# mouse.net
KiCad netlist of a schematic drawn in Altium Designer
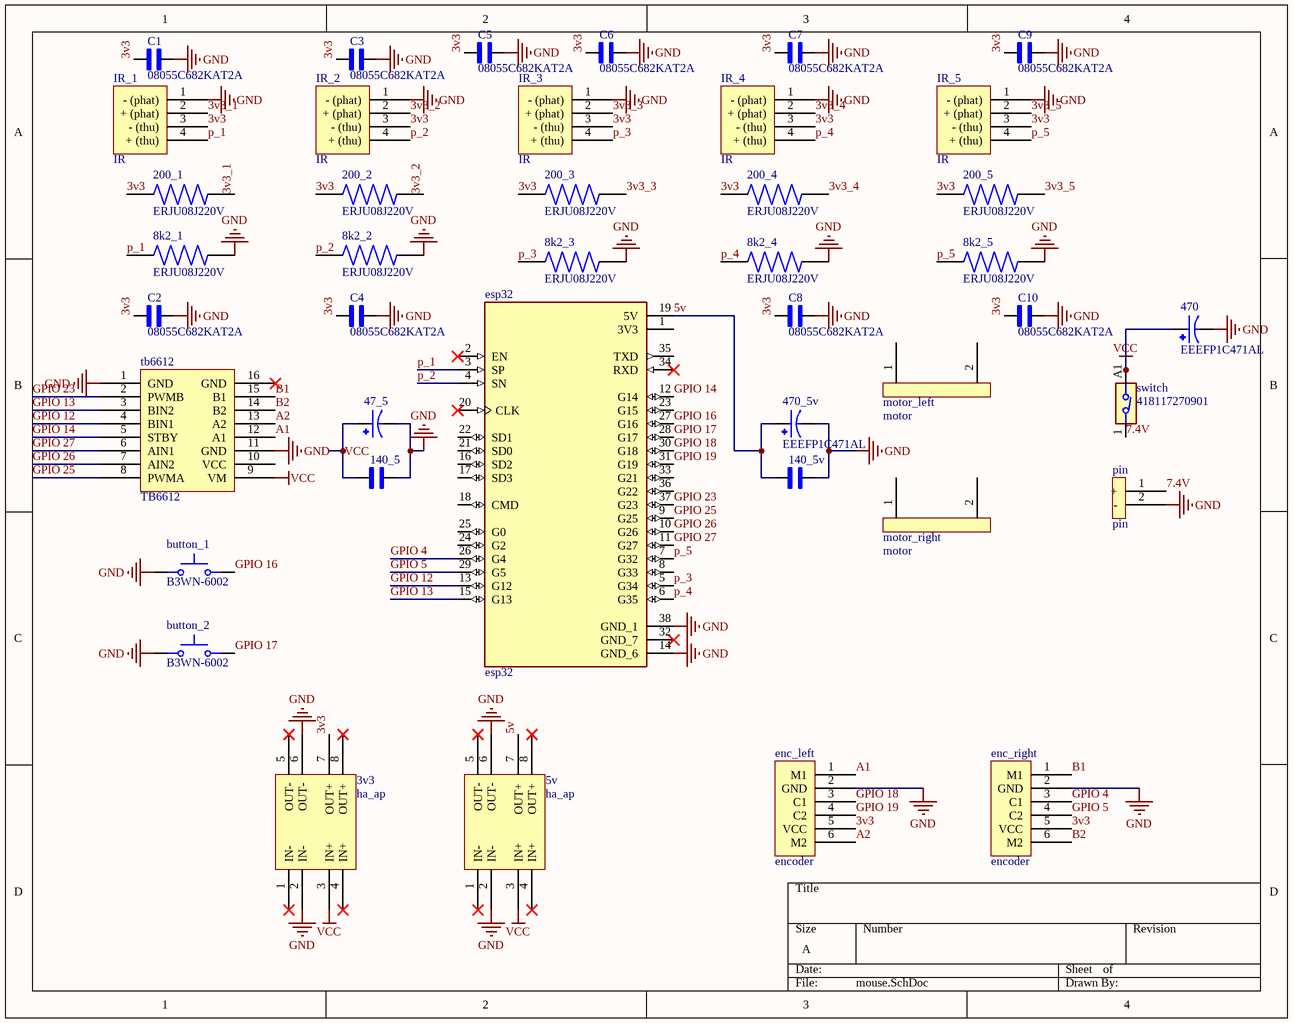
[diagram p0: mouse.SchDoc]

(export (version "E")
  (design (tool "Eeschema 10.0.6"))
  (components
    (comp (ref "3v3") (value "ha_ap") (footprint "ha_ap") (libsource (lib "mouse") (part "ha_ap")))
    (comp (ref "5v") (value "ha_ap") (footprint "ha_ap") (libsource (lib "mouse") (part "ha_ap")))
    (comp (ref "8k2_1")
      (value "ERJU08J220V")
      (footprint "RES_ERJU08J220V")
      (libsource (lib "ERJU08J220V") (part "ERJU08J220V"))
    )
    (comp (ref "8k2_2")
      (value "ERJU08J220V")
      (footprint "RES_ERJU08J220V")
      (libsource (lib "ERJU08J220V") (part "ERJU08J220V"))
    )
    (comp (ref "8k2_3")
      (value "ERJU08J220V")
      (footprint "RES_ERJU08J220V")
      (libsource (lib "ERJU08J220V") (part "ERJU08J220V"))
    )
    (comp (ref "8k2_4")
      (value "ERJU08J220V")
      (footprint "RES_ERJU08J220V")
      (libsource (lib "ERJU08J220V") (part "ERJU08J220V"))
    )
    (comp (ref "8k2_5")
      (value "ERJU08J220V")
      (footprint "RES_ERJU08J220V")
      (libsource (lib "ERJU08J220V") (part "ERJU08J220V"))
    )
    (comp (ref "47_5")
      (value "EEEFK1C470V")
      (footprint "CAP_EEEFK1C470V")
      (description "CAP ALUM 47UF 20% 16V SMD")
      (fields (field (name "MF") "Panasonic"))
      (libsource (lib "EEEFK1C470V") (part "EEEFK1C470V"))
    )
    (comp (ref "140_5")
      (value "08055C682KAT2A")
      (footprint "CAPC2012X94N")
      (description "Capacitor MLCC 0805 6.8nF 50V ¦ AVX 08055C682KAT2A")
      (fields (field (name "MF") "AVX"))
      (libsource (lib "08055C682KAT2A") (part "08055C682KAT2A"))
    )
    (comp (ref "140_5v")
      (value "08055C682KAT2A")
      (footprint "CAPC2012X94N")
      (description "Capacitor MLCC 0805 6.8nF 50V ¦ AVX 08055C682KAT2A")
      (fields (field (name "MF") "AVX"))
      (libsource (lib "08055C682KAT2A") (part "08055C682KAT2A"))
    )
    (comp (ref "200_1")
      (value "ERJU08J220V")
      (footprint "RES_ERJU08J220V")
      (libsource (lib "ERJU08J220V") (part "ERJU08J220V"))
    )
    (comp (ref "200_2")
      (value "ERJU08J220V")
      (footprint "RES_ERJU08J220V")
      (libsource (lib "ERJU08J220V") (part "ERJU08J220V"))
    )
    (comp (ref "200_3")
      (value "ERJU08J220V")
      (footprint "RES_ERJU08J220V")
      (libsource (lib "ERJU08J220V") (part "ERJU08J220V"))
    )
    (comp (ref "200_4")
      (value "ERJU08J220V")
      (footprint "RES_ERJU08J220V")
      (libsource (lib "ERJU08J220V") (part "ERJU08J220V"))
    )
    (comp (ref "200_5")
      (value "ERJU08J220V")
      (footprint "RES_ERJU08J220V")
      (libsource (lib "ERJU08J220V") (part "ERJU08J220V"))
    )
    (comp (ref "470")
      (value "EEEFP1C471AL")
      (footprint "CAP_EEEFP1C471AL")
      (description "CAP ALUM 470UF 20% 16V SMD")
      (fields (field (name "MF") "Panasonic"))
      (libsource (lib "EEEFP1C471AL") (part "EEEFP1C471AL"))
    )
    (comp (ref "470_5v")
      (value "EEEFP1C471AL")
      (footprint "CAP_EEEFP1C471AL")
      (description "CAP ALUM 470UF 20% 16V SMD")
      (fields (field (name "MF") "Panasonic"))
      (libsource (lib "EEEFP1C471AL") (part "EEEFP1C471AL"))
    )
    (comp (ref "button_1")
      (value "B3WN-6002")
      (footprint "SW_B3WN-6002")
      (description "Tactile Switch SPST-NO Top Actuated Through Hole")
      (fields (field (name "MF") "Omron Electronics"))
      (libsource (lib "B3WN-6002") (part "B3WN-6002"))
    )
    (comp (ref "button_2")
      (value "B3WN-6002")
      (footprint "SW_B3WN-6002")
      (description "Tactile Switch SPST-NO Top Actuated Through Hole")
      (fields (field (name "MF") "Omron Electronics"))
      (libsource (lib "B3WN-6002") (part "B3WN-6002"))
    )
    (comp (ref "C1")
      (value "08055C682KAT2A")
      (footprint "CAPC2012X94N")
      (description "Capacitor MLCC 0805 6.8nF 50V ¦ AVX 08055C682KAT2A")
      (fields (field (name "MF") "AVX"))
      (libsource (lib "08055C682KAT2A") (part "08055C682KAT2A"))
    )
    (comp (ref "C2")
      (value "08055C682KAT2A")
      (footprint "CAPC2012X94N")
      (description "Capacitor MLCC 0805 6.8nF 50V ¦ AVX 08055C682KAT2A")
      (fields (field (name "MF") "AVX"))
      (libsource (lib "08055C682KAT2A") (part "08055C682KAT2A"))
    )
    (comp (ref "C3")
      (value "08055C682KAT2A")
      (footprint "CAPC2012X94N")
      (description "Capacitor MLCC 0805 6.8nF 50V ¦ AVX 08055C682KAT2A")
      (fields (field (name "MF") "AVX"))
      (libsource (lib "08055C682KAT2A") (part "08055C682KAT2A"))
    )
    (comp (ref "C4")
      (value "08055C682KAT2A")
      (footprint "CAPC2012X94N")
      (description "Capacitor MLCC 0805 6.8nF 50V ¦ AVX 08055C682KAT2A")
      (fields (field (name "MF") "AVX"))
      (libsource (lib "08055C682KAT2A") (part "08055C682KAT2A"))
    )
    (comp (ref "C5")
      (value "08055C682KAT2A")
      (footprint "CAPC2012X94N")
      (description "Capacitor MLCC 0805 6.8nF 50V ¦ AVX 08055C682KAT2A")
      (fields (field (name "MF") "AVX"))
      (libsource (lib "08055C682KAT2A") (part "08055C682KAT2A"))
    )
    (comp (ref "C6")
      (value "08055C682KAT2A")
      (footprint "CAPC2012X94N")
      (description "Capacitor MLCC 0805 6.8nF 50V ¦ AVX 08055C682KAT2A")
      (fields (field (name "MF") "AVX"))
      (libsource (lib "08055C682KAT2A") (part "08055C682KAT2A"))
    )
    (comp (ref "C7")
      (value "08055C682KAT2A")
      (footprint "CAPC2012X94N")
      (description "Capacitor MLCC 0805 6.8nF 50V ¦ AVX 08055C682KAT2A")
      (fields (field (name "MF") "AVX"))
      (libsource (lib "08055C682KAT2A") (part "08055C682KAT2A"))
    )
    (comp (ref "C8")
      (value "08055C682KAT2A")
      (footprint "CAPC2012X94N")
      (description "Capacitor MLCC 0805 6.8nF 50V ¦ AVX 08055C682KAT2A")
      (fields (field (name "MF") "AVX"))
      (libsource (lib "08055C682KAT2A") (part "08055C682KAT2A"))
    )
    (comp (ref "C9")
      (value "08055C682KAT2A")
      (footprint "CAPC2012X94N")
      (description "Capacitor MLCC 0805 6.8nF 50V ¦ AVX 08055C682KAT2A")
      (fields (field (name "MF") "AVX"))
      (libsource (lib "08055C682KAT2A") (part "08055C682KAT2A"))
    )
    (comp (ref "C10")
      (value "08055C682KAT2A")
      (footprint "CAPC2012X94N")
      (description "Capacitor MLCC 0805 6.8nF 50V ¦ AVX 08055C682KAT2A")
      (fields (field (name "MF") "AVX"))
      (libsource (lib "08055C682KAT2A") (part "08055C682KAT2A"))
    )
    (comp (ref "enc_left") (value "encoder") (footprint "encoder") (libsource (lib "mouse") (part "encoder")))
    (comp (ref "enc_right")
      (value "encoder")
      (footprint "encoder")
      (libsource (lib "mouse") (part "encoder"))
    )
    (comp (ref "esp32") (value "esp32") (footprint "esp32") (libsource (lib "mouse") (part "esp32")))
    (comp (ref "IR_1") (value "IR") (footprint "IR") (libsource (lib "mouse") (part "IR")))
    (comp (ref "IR_2") (value "IR") (footprint "IR") (libsource (lib "mouse") (part "IR")))
    (comp (ref "IR_3") (value "IR") (footprint "IR") (libsource (lib "mouse") (part "IR")))
    (comp (ref "IR_4") (value "IR") (footprint "IR") (libsource (lib "mouse") (part "IR")))
    (comp (ref "IR_5") (value "IR") (footprint "IR") (libsource (lib "mouse") (part "IR")))
    (comp (ref "motor_left") (value "motor") (footprint "motor") (libsource (lib "mouse") (part "motor")))
    (comp (ref "motor_right") (value "motor") (footprint "motor") (libsource (lib "mouse") (part "motor")))
    (comp (ref "pin") (value "pin") (footprint "pin") (libsource (lib "mouse") (part "pin")))
    (comp (ref "switch")
      (value "418117270901")
      (footprint "418117270901")
      (description "Dip Switch SPST 1 Position Through Hole Slide (Standard) Actuator 25mA 24VDC")
      (fields (field (name "MF") "WÃ¼rth Elektronik"))
      (libsource (lib "418117270901") (part "418117270901"))
    )
    (comp (ref "tb6612") (value "TB6612") (footprint "TB6612") (libsource (lib "mouse") (part "TB6612")))
  )
  (nets
    (net (code "1") (name "/3v3") (class "Default")
      (node (ref "200_1") (pin "1") (pinfunction "1_1") (pintype "passive"))
      (node (ref "200_2") (pin "1") (pinfunction "1_1") (pintype "passive"))
      (node (ref "200_3") (pin "1") (pinfunction "1_1") (pintype "passive"))
      (node (ref "200_4") (pin "1") (pinfunction "1_1") (pintype "passive"))
      (node (ref "200_5") (pin "1") (pinfunction "1_1") (pintype "passive"))
      (node (ref "3v3") (pin "7") (pinfunction "OUT+_7") (pintype "passive"))
      (node (ref "C1") (pin "1") (pinfunction "1_1") (pintype "passive"))
      (node (ref "C10") (pin "1") (pinfunction "1_1") (pintype "passive"))
      (node (ref "C2") (pin "1") (pinfunction "1_1") (pintype "passive"))
      (node (ref "C3") (pin "1") (pinfunction "1_1") (pintype "passive"))
      (node (ref "C4") (pin "1") (pinfunction "1_1") (pintype "passive"))
      (node (ref "C5") (pin "1") (pinfunction "1_1") (pintype "passive"))
      (node (ref "C6") (pin "1") (pinfunction "1_1") (pintype "passive"))
      (node (ref "C7") (pin "1") (pinfunction "1_1") (pintype "passive"))
      (node (ref "C8") (pin "1") (pinfunction "1_1") (pintype "passive"))
      (node (ref "C9") (pin "1") (pinfunction "1_1") (pintype "passive"))
      (node (ref "IR_1") (pin "3") (pinfunction "-_(thu)_3") (pintype "passive"))
      (node (ref "IR_2") (pin "3") (pinfunction "-_(thu)_3") (pintype "passive"))
      (node (ref "IR_3") (pin "3") (pinfunction "-_(thu)_3") (pintype "passive"))
      (node (ref "IR_4") (pin "3") (pinfunction "-_(thu)_3") (pintype "passive"))
      (node (ref "IR_5") (pin "3") (pinfunction "-_(thu)_3") (pintype "passive"))
      (node (ref "enc_left") (pin "5") (pinfunction "VCC_5") (pintype "passive"))
      (node (ref "enc_right") (pin "5") (pinfunction "VCC_5") (pintype "passive"))
    )
    (net (code "2") (name "/3v3_1") (class "Default")
      (node (ref "200_1") (pin "2") (pinfunction "2_2") (pintype "passive"))
      (node (ref "IR_1") (pin "2") (pinfunction "+_(phat)_2") (pintype "passive"))
    )
    (net (code "3") (name "/3v3_2") (class "Default")
      (node (ref "200_2") (pin "2") (pinfunction "2_2") (pintype "passive"))
      (node (ref "IR_2") (pin "2") (pinfunction "+_(phat)_2") (pintype "passive"))
    )
    (net (code "4") (name "/3v3_3") (class "Default")
      (node (ref "200_3") (pin "2") (pinfunction "2_2") (pintype "passive"))
      (node (ref "IR_3") (pin "2") (pinfunction "+_(phat)_2") (pintype "passive"))
    )
    (net (code "5") (name "/3v3_4") (class "Default")
      (node (ref "200_4") (pin "2") (pinfunction "2_2") (pintype "passive"))
      (node (ref "IR_4") (pin "2") (pinfunction "+_(phat)_2") (pintype "passive"))
    )
    (net (code "6") (name "/3v3_5") (class "Default")
      (node (ref "200_5") (pin "2") (pinfunction "2_2") (pintype "passive"))
      (node (ref "IR_5") (pin "2") (pinfunction "+_(phat)_2") (pintype "passive"))
    )
    (net (code "7") (name "/5v") (class "Default")
      (node (ref "140_5v") (pin "1") (pinfunction "1_1") (pintype "passive"))
      (node (ref "470_5v") (pin "1") (pinfunction "1_1") (pintype "passive"))
      (node (ref "5v") (pin "7") (pinfunction "OUT+_7") (pintype "passive"))
      (node (ref "esp32") (pin "19") (pinfunction "5V_19") (pintype "power_in"))
    )
    (net (code "8") (name "/7.4V") (class "Default")
      (node (ref "pin") (pin "1") (pinfunction "+_1") (pintype "passive"))
      (node (ref "switch") (pin "1") (pinfunction "1_1") (pintype "passive"))
    )
    (net (code "9") (name "/A1") (class "Default")
      (node (ref "enc_left") (pin "1") (pinfunction "M1_1") (pintype "passive"))
      (node (ref "tb6612") (pin "12") (pinfunction "A1_12") (pintype "passive"))
    )
    (net (code "10") (name "/A2") (class "Default")
      (node (ref "enc_left") (pin "6") (pinfunction "M2_6") (pintype "passive"))
      (node (ref "tb6612") (pin "13") (pinfunction "A2_13") (pintype "passive"))
    )
    (net (code "11") (name "/B1") (class "Default")
      (node (ref "enc_right") (pin "1") (pinfunction "M1_1") (pintype "passive"))
      (node (ref "tb6612") (pin "15") (pinfunction "B1_15") (pintype "passive"))
    )
    (net (code "12") (name "/B2") (class "Default")
      (node (ref "enc_right") (pin "6") (pinfunction "M2_6") (pintype "passive"))
      (node (ref "tb6612") (pin "14") (pinfunction "B2_14") (pintype "passive"))
    )
    (net (code "13") (name "/GPIO 4") (class "Default")
      (node (ref "enc_right") (pin "3") (pinfunction "C1_3") (pintype "passive"))
      (node (ref "esp32") (pin "26") (pinfunction "G4_26") (pintype "bidirectional"))
    )
    (net (code "14") (name "/GPIO 5") (class "Default")
      (node (ref "enc_right") (pin "4") (pinfunction "C2_4") (pintype "passive"))
      (node (ref "esp32") (pin "29") (pinfunction "G5_29") (pintype "bidirectional"))
    )
    (net (code "15") (name "/GPIO 12") (class "Default")
      (node (ref "esp32") (pin "13") (pinfunction "G12_13") (pintype "bidirectional"))
      (node (ref "tb6612") (pin "4") (pinfunction "BIN1_4") (pintype "passive"))
    )
    (net (code "16") (name "/GPIO 13") (class "Default")
      (node (ref "esp32") (pin "15") (pinfunction "G13_15") (pintype "bidirectional"))
      (node (ref "tb6612") (pin "3") (pinfunction "BIN2_3") (pintype "passive"))
    )
    (net (code "17") (name "/GPIO 14") (class "Default")
      (node (ref "esp32") (pin "12") (pinfunction "G14_12") (pintype "bidirectional"))
      (node (ref "tb6612") (pin "5") (pinfunction "STBY_5") (pintype "passive"))
    )
    (net (code "18") (name "/GPIO 16") (class "Default")
      (node (ref "button_1") (pin "2") (pinfunction "2_2") (pintype "passive"))
      (node (ref "esp32") (pin "27") (pinfunction "G16_27") (pintype "bidirectional"))
    )
    (net (code "19") (name "/GPIO 17") (class "Default")
      (node (ref "button_2") (pin "2") (pinfunction "2_2") (pintype "passive"))
      (node (ref "esp32") (pin "28") (pinfunction "G17_28") (pintype "bidirectional"))
    )
    (net (code "20") (name "/GPIO 18") (class "Default")
      (node (ref "enc_left") (pin "3") (pinfunction "C1_3") (pintype "passive"))
      (node (ref "esp32") (pin "30") (pinfunction "G18_30") (pintype "bidirectional"))
    )
    (net (code "21") (name "/GPIO 19") (class "Default")
      (node (ref "enc_left") (pin "4") (pinfunction "C2_4") (pintype "passive"))
      (node (ref "esp32") (pin "31") (pinfunction "G19_31") (pintype "bidirectional"))
    )
    (net (code "22") (name "/GPIO 23") (class "Default")
      (node (ref "esp32") (pin "37") (pinfunction "G23_37") (pintype "bidirectional"))
      (node (ref "tb6612") (pin "2") (pinfunction "PWMB_2") (pintype "passive"))
    )
    (net (code "23") (name "/GPIO 25") (class "Default")
      (node (ref "esp32") (pin "9") (pinfunction "G25_9") (pintype "bidirectional"))
      (node (ref "tb6612") (pin "8") (pinfunction "PWMA_8") (pintype "passive"))
    )
    (net (code "24") (name "/GPIO 26") (class "Default")
      (node (ref "esp32") (pin "10") (pinfunction "G26_10") (pintype "bidirectional"))
      (node (ref "tb6612") (pin "7") (pinfunction "AIN2_7") (pintype "passive"))
    )
    (net (code "25") (name "/GPIO 27") (class "Default")
      (node (ref "esp32") (pin "11") (pinfunction "G27_11") (pintype "bidirectional"))
      (node (ref "tb6612") (pin "6") (pinfunction "AIN1_6") (pintype "passive"))
    )
    (net (code "26") (name "/p_1") (class "Default")
      (node (ref "8k2_1") (pin "1") (pinfunction "1_1") (pintype "passive"))
      (node (ref "IR_1") (pin "4") (pinfunction "+_(thu)_4") (pintype "passive"))
      (node (ref "esp32") (pin "3") (pinfunction "SP_3") (pintype "input"))
    )
    (net (code "27") (name "/p_2") (class "Default")
      (node (ref "8k2_2") (pin "1") (pinfunction "1_1") (pintype "passive"))
      (node (ref "IR_2") (pin "4") (pinfunction "+_(thu)_4") (pintype "passive"))
      (node (ref "esp32") (pin "4") (pinfunction "SN_4") (pintype "input"))
    )
    (net (code "28") (name "/p_3") (class "Default")
      (node (ref "8k2_3") (pin "1") (pinfunction "1_1") (pintype "passive"))
      (node (ref "IR_3") (pin "4") (pinfunction "+_(thu)_4") (pintype "passive"))
      (node (ref "esp32") (pin "5") (pinfunction "G34_5") (pintype "bidirectional"))
    )
    (net (code "29") (name "/p_4") (class "Default")
      (node (ref "8k2_4") (pin "1") (pinfunction "1_1") (pintype "passive"))
      (node (ref "IR_4") (pin "4") (pinfunction "+_(thu)_4") (pintype "passive"))
      (node (ref "esp32") (pin "6") (pinfunction "G35_6") (pintype "bidirectional"))
    )
    (net (code "30") (name "/p_5") (class "Default")
      (node (ref "8k2_5") (pin "1") (pinfunction "1_1") (pintype "passive"))
      (node (ref "IR_5") (pin "4") (pinfunction "+_(thu)_4") (pintype "passive"))
      (node (ref "esp32") (pin "7") (pinfunction "G32_7") (pintype "bidirectional"))
    )
    (net (code "31") (name "GND") (class "Default")
      (node (ref "140_5") (pin "2") (pinfunction "2_2") (pintype "passive"))
      (node (ref "140_5v") (pin "2") (pinfunction "2_2") (pintype "passive"))
      (node (ref "3v3") (pin "2") (pinfunction "IN-_2") (pintype "passive"))
      (node (ref "3v3") (pin "6") (pinfunction "OUT-_6") (pintype "passive"))
      (node (ref "470") (pin "2") (pinfunction "2_2") (pintype "passive"))
      (node (ref "470_5v") (pin "2") (pinfunction "2_2") (pintype "passive"))
      (node (ref "47_5") (pin "2") (pinfunction "2_2") (pintype "passive"))
      (node (ref "5v") (pin "2") (pinfunction "IN-_2") (pintype "passive"))
      (node (ref "5v") (pin "6") (pinfunction "OUT-_6") (pintype "passive"))
      (node (ref "8k2_1") (pin "2") (pinfunction "2_2") (pintype "passive"))
      (node (ref "8k2_2") (pin "2") (pinfunction "2_2") (pintype "passive"))
      (node (ref "8k2_3") (pin "2") (pinfunction "2_2") (pintype "passive"))
      (node (ref "8k2_4") (pin "2") (pinfunction "2_2") (pintype "passive"))
      (node (ref "8k2_5") (pin "2") (pinfunction "2_2") (pintype "passive"))
      (node (ref "C1") (pin "2") (pinfunction "2_2") (pintype "passive"))
      (node (ref "C10") (pin "2") (pinfunction "2_2") (pintype "passive"))
      (node (ref "C2") (pin "2") (pinfunction "2_2") (pintype "passive"))
      (node (ref "C3") (pin "2") (pinfunction "2_2") (pintype "passive"))
      (node (ref "C4") (pin "2") (pinfunction "2_2") (pintype "passive"))
      (node (ref "C5") (pin "2") (pinfunction "2_2") (pintype "passive"))
      (node (ref "C6") (pin "2") (pinfunction "2_2") (pintype "passive"))
      (node (ref "C7") (pin "2") (pinfunction "2_2") (pintype "passive"))
      (node (ref "C8") (pin "2") (pinfunction "2_2") (pintype "passive"))
      (node (ref "C9") (pin "2") (pinfunction "2_2") (pintype "passive"))
      (node (ref "IR_1") (pin "1") (pinfunction "-_(phat)_1") (pintype "passive"))
      (node (ref "IR_2") (pin "1") (pinfunction "-_(phat)_1") (pintype "passive"))
      (node (ref "IR_3") (pin "1") (pinfunction "-_(phat)_1") (pintype "passive"))
      (node (ref "IR_4") (pin "1") (pinfunction "-_(phat)_1") (pintype "passive"))
      (node (ref "IR_5") (pin "1") (pinfunction "-_(phat)_1") (pintype "passive"))
      (node (ref "button_1") (pin "1") (pinfunction "1_1") (pintype "passive"))
      (node (ref "button_2") (pin "1") (pinfunction "1_1") (pintype "passive"))
      (node (ref "enc_left") (pin "2") (pinfunction "GND_2") (pintype "passive"))
      (node (ref "enc_right") (pin "2") (pinfunction "GND_2") (pintype "passive"))
      (node (ref "esp32") (pin "14") (pinfunction "GND_6_14") (pintype "power_in"))
      (node (ref "esp32") (pin "38") (pinfunction "GND_1_38") (pintype "power_in"))
      (node (ref "pin") (pin "2") (pinfunction "-_2") (pintype "passive"))
      (node (ref "tb6612") (pin "1") (pinfunction "GND_1") (pintype "passive"))
      (node (ref "tb6612") (pin "11") (pinfunction "GND_11") (pintype "passive"))
    )
    (net (code "32") (name "VCC") (class "Default")
      (node (ref "140_5") (pin "1") (pinfunction "1_1") (pintype "passive"))
      (node (ref "3v3") (pin "3") (pinfunction "IN+_3") (pintype "passive"))
      (node (ref "470") (pin "1") (pinfunction "1_1") (pintype "passive"))
      (node (ref "47_5") (pin "1") (pinfunction "1_1") (pintype "passive"))
      (node (ref "5v") (pin "3") (pinfunction "IN+_3") (pintype "passive"))
      (node (ref "switch") (pin "A1") (pinfunction "A1_A1") (pintype "passive"))
      (node (ref "tb6612") (pin "9") (pinfunction "VM_9") (pintype "passive"))
    )
    (net (code "33") (name "unconnected-(3v3-IN+-Pad4)") (class "Default")
      (node (ref "3v3") (pin "4") (pinfunction "IN+_4") (pintype "passive+no_connect"))
    )
    (net (code "34") (name "unconnected-(3v3-IN--Pad1)") (class "Default")
      (node (ref "3v3") (pin "1") (pinfunction "IN-_1") (pintype "passive+no_connect"))
    )
    (net (code "35") (name "unconnected-(3v3-OUT+-Pad8)") (class "Default")
      (node (ref "3v3") (pin "8") (pinfunction "OUT+_8") (pintype "passive+no_connect"))
    )
    (net (code "36") (name "unconnected-(3v3-OUT--Pad5)") (class "Default")
      (node (ref "3v3") (pin "5") (pinfunction "OUT-_5") (pintype "passive+no_connect"))
    )
    (net (code "37") (name "unconnected-(5v-IN+-Pad4)") (class "Default")
      (node (ref "5v") (pin "4") (pinfunction "IN+_4") (pintype "passive+no_connect"))
    )
    (net (code "38") (name "unconnected-(5v-IN--Pad1)") (class "Default")
      (node (ref "5v") (pin "1") (pinfunction "IN-_1") (pintype "passive+no_connect"))
    )
    (net (code "39") (name "unconnected-(5v-OUT+-Pad8)") (class "Default")
      (node (ref "5v") (pin "8") (pinfunction "OUT+_8") (pintype "passive+no_connect"))
    )
    (net (code "40") (name "unconnected-(5v-OUT--Pad5)") (class "Default")
      (node (ref "5v") (pin "5") (pinfunction "OUT-_5") (pintype "passive+no_connect"))
    )
    (net (code "41") (name "unconnected-(esp32-3V3-Pad1)") (class "Default")
      (node (ref "esp32") (pin "1") (pinfunction "3V3_1") (pintype "power_in"))
    )
    (net (code "42") (name "unconnected-(esp32-CLK-Pad20)") (class "Default")
      (node (ref "esp32") (pin "20") (pinfunction "CLK_20") (pintype "input+no_connect"))
    )
    (net (code "43") (name "unconnected-(esp32-CMD-Pad18)") (class "Default")
      (node (ref "esp32") (pin "18") (pinfunction "CMD_18") (pintype "bidirectional"))
    )
    (net (code "44") (name "unconnected-(esp32-EN-Pad2)") (class "Default")
      (node (ref "esp32") (pin "2") (pinfunction "EN_2") (pintype "input+no_connect"))
    )
    (net (code "45") (name "unconnected-(esp32-G0-Pad25)") (class "Default")
      (node (ref "esp32") (pin "25") (pinfunction "G0_25") (pintype "bidirectional"))
    )
    (net (code "46") (name "unconnected-(esp32-G2-Pad24)") (class "Default")
      (node (ref "esp32") (pin "24") (pinfunction "G2_24") (pintype "bidirectional"))
    )
    (net (code "47") (name "unconnected-(esp32-G15-Pad23)") (class "Default")
      (node (ref "esp32") (pin "23") (pinfunction "G15_23") (pintype "bidirectional"))
    )
    (net (code "48") (name "unconnected-(esp32-G21-Pad33)") (class "Default")
      (node (ref "esp32") (pin "33") (pinfunction "G21_33") (pintype "bidirectional"))
    )
    (net (code "49") (name "unconnected-(esp32-G22-Pad36)") (class "Default")
      (node (ref "esp32") (pin "36") (pinfunction "G22_36") (pintype "bidirectional"))
    )
    (net (code "50") (name "unconnected-(esp32-G33-Pad8)") (class "Default")
      (node (ref "esp32") (pin "8") (pinfunction "G33_8") (pintype "bidirectional"))
    )
    (net (code "51") (name "unconnected-(esp32-GND_7-Pad32)") (class "Default")
      (node (ref "esp32") (pin "32") (pinfunction "GND_7_32") (pintype "power_in+no_connect"))
    )
    (net (code "52") (name "unconnected-(esp32-RXD-Pad34)") (class "Default")
      (node (ref "esp32") (pin "34") (pinfunction "RXD_34") (pintype "input+no_connect"))
    )
    (net (code "53") (name "unconnected-(esp32-SD0-Pad21)") (class "Default")
      (node (ref "esp32") (pin "21") (pinfunction "SD0_21") (pintype "bidirectional"))
    )
    (net (code "54") (name "unconnected-(esp32-SD1-Pad22)") (class "Default")
      (node (ref "esp32") (pin "22") (pinfunction "SD1_22") (pintype "bidirectional"))
    )
    (net (code "55") (name "unconnected-(esp32-SD2-Pad16)") (class "Default")
      (node (ref "esp32") (pin "16") (pinfunction "SD2_16") (pintype "bidirectional"))
    )
    (net (code "56") (name "unconnected-(esp32-SD3-Pad17)") (class "Default")
      (node (ref "esp32") (pin "17") (pinfunction "SD3_17") (pintype "bidirectional"))
    )
    (net (code "57") (name "unconnected-(esp32-TXD-Pad35)") (class "Default")
      (node (ref "esp32") (pin "35") (pinfunction "TXD_35") (pintype "output"))
    )
    (net (code "58") (name "unconnected-(motor_left-40-Pad2)") (class "Default")
      (node (ref "motor_left") (pin "2") (pinfunction "40_2") (pintype "passive"))
    )
    (net (code "59") (name "unconnected-(motor_left-41-Pad1)") (class "Default")
      (node (ref "motor_left") (pin "1") (pinfunction "41_1") (pintype "passive"))
    )
    (net (code "60") (name "unconnected-(motor_right-40-Pad2)") (class "Default")
      (node (ref "motor_right") (pin "2") (pinfunction "40_2") (pintype "passive"))
    )
    (net (code "61") (name "unconnected-(motor_right-41-Pad1)") (class "Default")
      (node (ref "motor_right") (pin "1") (pinfunction "41_1") (pintype "passive"))
    )
    (net (code "62") (name "unconnected-(tb6612-GND-Pad16)") (class "Default")
      (node (ref "tb6612") (pin "16") (pinfunction "GND_16") (pintype "passive+no_connect"))
    )
    (net (code "63") (name "unconnected-(tb6612-VCC-Pad10)") (class "Default")
      (node (ref "tb6612") (pin "10") (pinfunction "VCC_10") (pintype "passive"))
    )
  )
)
